# krajBB-Moj_i__Matej_DONE.net
KiCad netlist of a schematic drawn in EAGLE
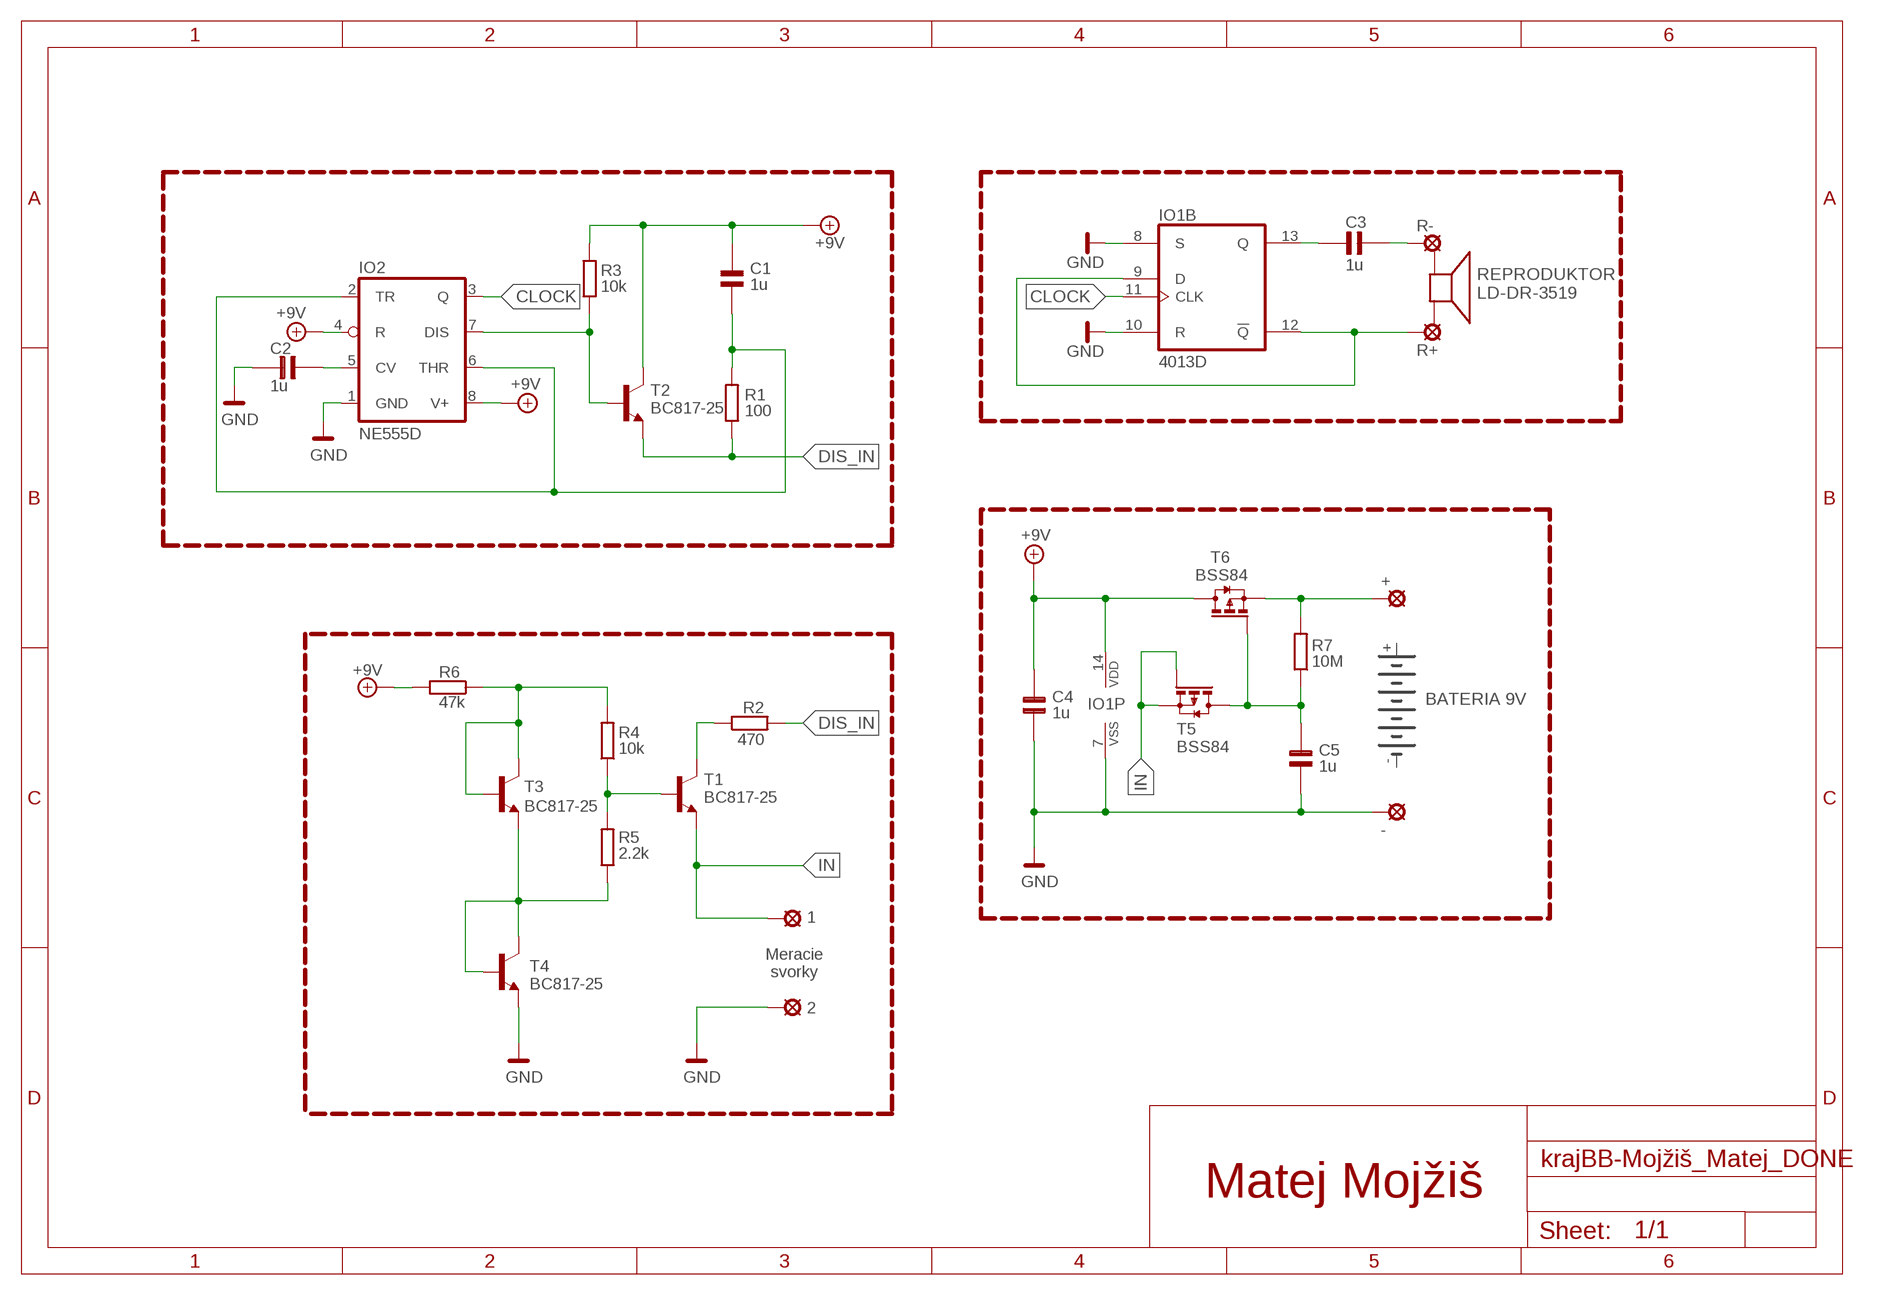
[diagram p0: schematic, sheet 1]

(export (version "E")
  (design (tool "Eeschema 10.0.6"))
  (components
    (comp (ref "+")
      (value "SMD3X3")
      (footprint "eagle-import:SMD3X3")
      (libsource (lib "eagle-import") (part "SMD3X3"))
    )
    (comp (ref "-")
      (value "SMD3X3")
      (footprint "eagle-import:SMD3X3")
      (libsource (lib "eagle-import") (part "SMD3X3"))
    )
    (comp (ref "1")
      (value "SMD3X3")
      (footprint "eagle-import:SMD3X3")
      (libsource (lib "eagle-import") (part "SMD3X3"))
    )
    (comp (ref "2")
      (value "SMD3X3")
      (footprint "eagle-import:SMD3X3")
      (libsource (lib "eagle-import") (part "SMD3X3"))
    )
    (comp (ref "C1")
      (value "1u")
      (footprint "eagle-import:1206")
      (libsource (lib "eagle-import") (part "C1206TOP"))
    )
    (comp (ref "C2")
      (value "1u")
      (footprint "eagle-import:1206")
      (libsource (lib "eagle-import") (part "C1206TOP"))
    )
    (comp (ref "C3")
      (value "1u")
      (footprint "eagle-import:1206")
      (libsource (lib "eagle-import") (part "C1206TOP"))
    )
    (comp (ref "C4")
      (value "1u")
      (footprint "eagle-import:1206")
      (libsource (lib "eagle-import") (part "C1206TOP"))
    )
    (comp (ref "C5")
      (value "1u")
      (footprint "eagle-import:1206")
      (libsource (lib "eagle-import") (part "C1206TOP"))
    )
    (comp (ref "IO1")
      (value "4013D")
      (footprint "eagle-import:SO14")
      (libsource (lib "eagle-import") (part "4013D"))
    )
    (comp (ref "IO2")
      (value "NE555D")
      (footprint "eagle-import:SO08")
      (libsource (lib "eagle-import") (part "555DNE"))
    )
    (comp (ref "R+")
      (value "SMD3X3")
      (footprint "eagle-import:SMD3X3")
      (libsource (lib "eagle-import") (part "SMD3X3"))
    )
    (comp (ref "R-")
      (value "SMD3X3")
      (footprint "eagle-import:SMD3X3")
      (libsource (lib "eagle-import") (part "SMD3X3"))
    )
    (comp (ref "R1")
      (value "100")
      (footprint "eagle-import:1206")
      (libsource (lib "eagle-import") (part "R1206TOP"))
    )
    (comp (ref "R2")
      (value "470")
      (footprint "eagle-import:1206")
      (libsource (lib "eagle-import") (part "R1206TOP"))
    )
    (comp (ref "R3")
      (value "10k")
      (footprint "eagle-import:1206")
      (libsource (lib "eagle-import") (part "R1206TOP"))
    )
    (comp (ref "R4")
      (value "10k")
      (footprint "eagle-import:1206")
      (libsource (lib "eagle-import") (part "R1206TOP"))
    )
    (comp (ref "R5")
      (value "2.2k")
      (footprint "eagle-import:1206")
      (libsource (lib "eagle-import") (part "R1206TOP"))
    )
    (comp (ref "R6")
      (value "47k")
      (footprint "eagle-import:1206")
      (libsource (lib "eagle-import") (part "R1206TOP"))
    )
    (comp (ref "R7")
      (value "10M")
      (footprint "eagle-import:1206")
      (libsource (lib "eagle-import") (part "R1206TOP"))
    )
    (comp (ref "REPRODUKTOR")
      (value "LD-DR-3519")
      (footprint "eagle-import:LD-DR-3519")
      (libsource (lib "eagle-import") (part "LD-DR-3519"))
    )
    (comp (ref "T1")
      (value "BC817-25")
      (footprint "eagle-import:SOT23-BEC")
      (libsource (lib "eagle-import") (part "BC817SMD-25"))
    )
    (comp (ref "T2")
      (value "BC817-25")
      (footprint "eagle-import:SOT23-BEC")
      (libsource (lib "eagle-import") (part "BC817SMD-25"))
    )
    (comp (ref "T3")
      (value "BC817-25")
      (footprint "eagle-import:SOT23-BEC")
      (libsource (lib "eagle-import") (part "BC817SMD-25"))
    )
    (comp (ref "T4")
      (value "BC817-25")
      (footprint "eagle-import:SOT23-BEC")
      (libsource (lib "eagle-import") (part "BC817SMD-25"))
    )
    (comp (ref "T5")
      (value "BSS84")
      (footprint "eagle-import:SOT23")
      (libsource (lib "eagle-import") (part "BSS84"))
    )
    (comp (ref "T6")
      (value "BSS84")
      (footprint "eagle-import:SOT23")
      (libsource (lib "eagle-import") (part "BSS84"))
    )
    (comp (ref "U$1")
      (value "9VBATTERY")
      (footprint "eagle-import:9VBATTERY")
      (libsource (lib "eagle-import") (part "9VBATTERY"))
    )
  )
  (nets
    (net (code "1") (name "+9V") (class "Default")
      (node (ref "C1") (pin "2") (pinfunction "2_2") (pintype "passive"))
      (node (ref "C4") (pin "2") (pinfunction "2_2") (pintype "passive"))
      (node (ref "IO1") (pin "14") (pinfunction "VDD_14") (pintype "power_in"))
      (node (ref "IO2") (pin "4") (pinfunction "R_4") (pintype "input"))
      (node (ref "IO2") (pin "8") (pinfunction "V+_8") (pintype "power_in"))
      (node (ref "R3") (pin "2") (pinfunction "2_2") (pintype "passive"))
      (node (ref "R6") (pin "2") (pinfunction "2_2") (pintype "passive"))
      (node (ref "T2") (pin "C") (pinfunction "C_C") (pintype "passive"))
      (node (ref "T6") (pin "3") (pinfunction "D_3") (pintype "passive"))
    )
    (net (code "2") (name "CLOCK") (class "Default")
      (node (ref "IO1") (pin "11") (pinfunction "CLK_11") (pintype "input"))
      (node (ref "IO2") (pin "3") (pinfunction "Q_3") (pintype "output"))
    )
    (net (code "3") (name "DIS_IN") (class "Default")
      (node (ref "R1") (pin "1") (pinfunction "1_1") (pintype "passive"))
      (node (ref "R2") (pin "2") (pinfunction "2_2") (pintype "passive"))
      (node (ref "T2") (pin "E") (pinfunction "E_E") (pintype "passive"))
    )
    (net (code "4") (name "GND") (class "Default")
      (node (ref "-") (pin "P$1") (pinfunction "MP_P$1") (pintype "passive"))
      (node (ref "2") (pin "P$1") (pinfunction "MP_P$1") (pintype "passive"))
      (node (ref "C2") (pin "1") (pinfunction "1_1") (pintype "passive"))
      (node (ref "C4") (pin "1") (pinfunction "1_1") (pintype "passive"))
      (node (ref "C5") (pin "1") (pinfunction "1_1") (pintype "passive"))
      (node (ref "IO1") (pin "10") (pinfunction "R_10") (pintype "input"))
      (node (ref "IO1") (pin "7") (pinfunction "VSS_7") (pintype "power_in"))
      (node (ref "IO1") (pin "8") (pinfunction "S_8") (pintype "input"))
      (node (ref "IO2") (pin "1") (pinfunction "GND_1") (pintype "power_in"))
      (node (ref "T4") (pin "E") (pinfunction "E_E") (pintype "passive"))
    )
    (net (code "5") (name "IN") (class "Default")
      (node (ref "1") (pin "P$1") (pinfunction "MP_P$1") (pintype "passive"))
      (node (ref "T1") (pin "E") (pinfunction "E_E") (pintype "passive"))
      (node (ref "T5") (pin "1") (pinfunction "G_1") (pintype "passive"))
      (node (ref "T5") (pin "2") (pinfunction "S_2") (pintype "passive"))
    )
    (net (code "6") (name "Net-(+-MP)") (class "Default")
      (node (ref "+") (pin "P$1") (pinfunction "MP_P$1") (pintype "passive"))
      (node (ref "R7") (pin "2") (pinfunction "2_2") (pintype "passive"))
      (node (ref "T6") (pin "2") (pinfunction "S_2") (pintype "passive"))
    )
    (net (code "7") (name "Net-(IO1B-D)") (class "Default")
      (node (ref "IO1") (pin "12") (pinfunction "~{Q}_12") (pintype "output"))
      (node (ref "IO1") (pin "9") (pinfunction "D_9") (pintype "input"))
      (node (ref "R+") (pin "P$1") (pinfunction "MP_P$1") (pintype "passive"))
    )
    (net (code "8") (name "Net-(IO1B-Q)") (class "Default")
      (node (ref "C3") (pin "1") (pinfunction "1_1") (pintype "passive"))
      (node (ref "IO1") (pin "13") (pinfunction "Q_13") (pintype "output"))
    )
    (net (code "9") (name "Net-(IO2-CV)") (class "Default")
      (node (ref "C2") (pin "2") (pinfunction "2_2") (pintype "passive"))
      (node (ref "IO2") (pin "5") (pinfunction "CV_5") (pintype "input"))
    )
    (net (code "10") (name "Net-(IO2-DIS)") (class "Default")
      (node (ref "IO2") (pin "7") (pinfunction "DIS_7") (pintype "input"))
      (node (ref "R3") (pin "1") (pinfunction "1_1") (pintype "passive"))
      (node (ref "T2") (pin "B") (pinfunction "B_B") (pintype "passive"))
    )
    (net (code "11") (name "Net-(IO2-THR)") (class "Default")
      (node (ref "C1") (pin "1") (pinfunction "1_1") (pintype "passive"))
      (node (ref "IO2") (pin "2") (pinfunction "TR_2") (pintype "input"))
      (node (ref "IO2") (pin "6") (pinfunction "THR_6") (pintype "input"))
      (node (ref "R1") (pin "2") (pinfunction "2_2") (pintype "passive"))
    )
    (net (code "12") (name "Net-(R--MP)") (class "Default")
      (node (ref "C3") (pin "2") (pinfunction "2_2") (pintype "passive"))
      (node (ref "R-") (pin "P$1") (pinfunction "MP_P$1") (pintype "passive"))
    )
    (net (code "13") (name "Net-(R2-Pad1)") (class "Default")
      (node (ref "R2") (pin "1") (pinfunction "1_1") (pintype "passive"))
      (node (ref "T1") (pin "C") (pinfunction "C_C") (pintype "passive"))
    )
    (net (code "14") (name "Net-(R4-Pad1)") (class "Default")
      (node (ref "R4") (pin "1") (pinfunction "1_1") (pintype "passive"))
      (node (ref "R5") (pin "2") (pinfunction "2_2") (pintype "passive"))
      (node (ref "T1") (pin "B") (pinfunction "B_B") (pintype "passive"))
    )
    (net (code "15") (name "Net-(R4-Pad2)") (class "Default")
      (node (ref "R4") (pin "2") (pinfunction "2_2") (pintype "passive"))
      (node (ref "R6") (pin "1") (pinfunction "1_1") (pintype "passive"))
      (node (ref "T3") (pin "B") (pinfunction "B_B") (pintype "passive"))
      (node (ref "T3") (pin "C") (pinfunction "C_C") (pintype "passive"))
    )
    (net (code "16") (name "Net-(R5-Pad1)") (class "Default")
      (node (ref "R5") (pin "1") (pinfunction "1_1") (pintype "passive"))
      (node (ref "T3") (pin "E") (pinfunction "E_E") (pintype "passive"))
      (node (ref "T4") (pin "B") (pinfunction "B_B") (pintype "passive"))
      (node (ref "T4") (pin "C") (pinfunction "C_C") (pintype "passive"))
    )
    (net (code "17") (name "Net-(T5-D)") (class "Default")
      (node (ref "C5") (pin "2") (pinfunction "2_2") (pintype "passive"))
      (node (ref "R7") (pin "1") (pinfunction "1_1") (pintype "passive"))
      (node (ref "T5") (pin "3") (pinfunction "D_3") (pintype "passive"))
      (node (ref "T6") (pin "1") (pinfunction "G_1") (pintype "passive"))
    )
    (net (code "18") (name "unconnected-(REPRODUKTOR-1-PadP$1)") (class "Default")
      (node (ref "REPRODUKTOR") (pin "P$1") (pinfunction "1_P$1") (pintype "passive"))
    )
    (net (code "19") (name "unconnected-(REPRODUKTOR-2-PadP$2)") (class "Default")
      (node (ref "REPRODUKTOR") (pin "P$2") (pinfunction "2_P$2") (pintype "passive"))
    )
  )
)
